# Connectors.net
KiCad netlist of a schematic drawn in Altium Designer
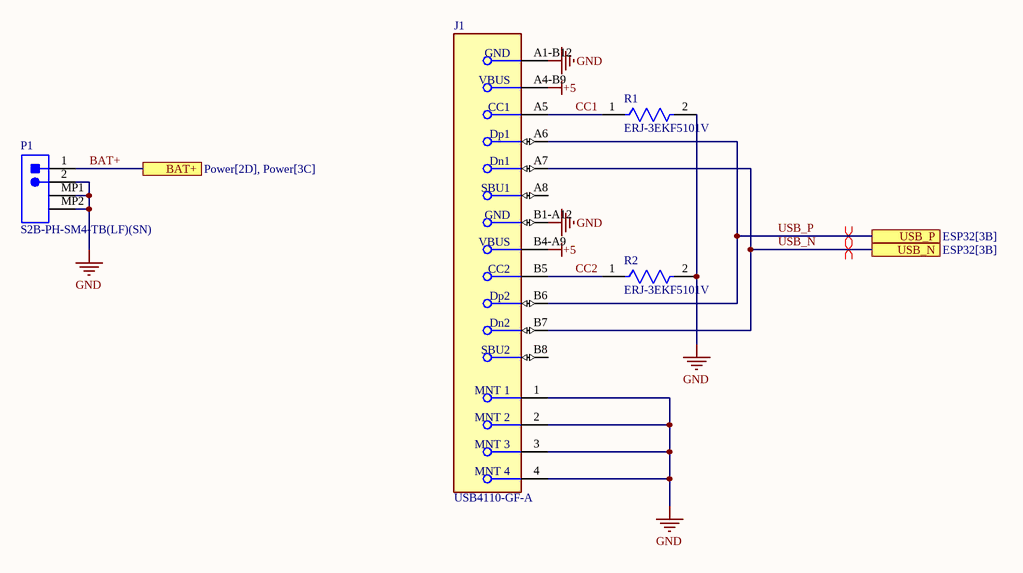
[diagram p0: Connectors.SchDoc]

(export (version "E")
  (design (tool "Eeschema 10.0.6"))
  (components
    (comp (ref "J1")
      (value "USB4110-GF-A")
      (footprint "FP-USB4110-GF-A-MFG")
      (description "CONN USB 2.0 TYPE-C R/A SMT")
      (fields
        (field (name "OCTOPART") "https://octopart.com/usb4110-gf-a-gct-103941985")
        (field (name "MANUFACTURER") "GCT")
      )
      (libsource (lib "Altium Content Vault") (part "e23f2b38bb3c3f98e683ebab9ede730"))
    )
    (comp (ref "P1")
      (value "S2B-PH-SM4-TB(LF)(SN)")
      (footprint "JST- S2B-PH-SM4-TB(LF)(SN)-2_V")
      (description "Male Header, Pitch 2 mm, 1 x 2 Position, Height 5.5 mm, -25 to 85 degC, RoHS, Tape and Reel")
      (libsource (lib "Altium Content Vault") (part "CN-1P-2M-R2"))
    )
    (comp (ref "R1")
      (value "ERJ-3EKF5101V")
      (footprint "FP-ERJ3EK-MFG")
      (description "RES SMD 5.1K OHM 1% 1/10W 0603")
      (fields (field (name "TOLERANCE") "1%"))
      (libsource (lib "Altium Content Vault") (part "1029c3af85768c4190bb7ad29bc67b5"))
    )
    (comp (ref "R2")
      (value "ERJ-3EKF5101V")
      (footprint "FP-ERJ3EK-MFG")
      (description "RES SMD 5.1K OHM 1% 1/10W 0603")
      (fields (field (name "TOLERANCE") "1%"))
      (libsource (lib "Altium Content Vault") (part "1029c3af85768c4190bb7ad29bc67b5"))
    )
  )
  (nets
    (net (code "1") (name "+5") (class "Default")
      (node (ref "J1") (pin "A4-B9") (pinfunction "VBUS_A4-B9") (pintype "power_in"))
      (node (ref "J1") (pin "B4-A9") (pinfunction "VBUS_B4-A9") (pintype "power_in"))
    )
    (net (code "2") (name "/BAT+") (class "Default")
      (node (ref "P1") (pin "1") (pinfunction "1_1") (pintype "passive"))
    )
    (net (code "3") (name "/CC1") (class "Default")
      (node (ref "J1") (pin "A5") (pinfunction "CC1_A5") (pintype "power_in"))
      (node (ref "R1") (pin "1") (pinfunction "1_1") (pintype "passive"))
    )
    (net (code "4") (name "/CC2") (class "Default")
      (node (ref "J1") (pin "B5") (pinfunction "CC2_B5") (pintype "power_in"))
      (node (ref "R2") (pin "1") (pinfunction "1_1") (pintype "passive"))
    )
    (net (code "5") (name "/USB_N") (class "Default")
      (node (ref "J1") (pin "A7") (pinfunction "Dn1_A7") (pintype "bidirectional"))
      (node (ref "J1") (pin "B7") (pinfunction "Dn2_B7") (pintype "bidirectional"))
    )
    (net (code "6") (name "/USB_P") (class "Default")
      (node (ref "J1") (pin "A6") (pinfunction "Dp1_A6") (pintype "bidirectional"))
      (node (ref "J1") (pin "B6") (pinfunction "Dp2_B6") (pintype "bidirectional"))
    )
    (net (code "7") (name "GND") (class "Default")
      (node (ref "J1") (pin "1") (pinfunction "MNT_1_1") (pintype "passive"))
      (node (ref "J1") (pin "2") (pinfunction "MNT_2_2") (pintype "passive"))
      (node (ref "J1") (pin "3") (pinfunction "MNT_3_3") (pintype "passive"))
      (node (ref "J1") (pin "4") (pinfunction "MNT_4_4") (pintype "passive"))
      (node (ref "J1") (pin "A1-B12") (pinfunction "GND_A1-B12") (pintype "passive"))
      (node (ref "J1") (pin "B1-A12") (pinfunction "GND_B1-A12") (pintype "bidirectional"))
      (node (ref "P1") (pin "2") (pinfunction "2_2") (pintype "passive"))
      (node (ref "P1") (pin "MP1") (pinfunction "MP1_MP1") (pintype "passive"))
      (node (ref "P1") (pin "MP2") (pinfunction "MP2_MP2") (pintype "passive"))
      (node (ref "R1") (pin "2") (pinfunction "2_2") (pintype "passive"))
      (node (ref "R2") (pin "2") (pinfunction "2_2") (pintype "passive"))
    )
    (net (code "8") (name "unconnected-(J1-SBU1-PadA8)") (class "Default")
      (node (ref "J1") (pin "A8") (pinfunction "SBU1_A8") (pintype "bidirectional"))
    )
    (net (code "9") (name "unconnected-(J1-SBU2-PadB8)") (class "Default")
      (node (ref "J1") (pin "B8") (pinfunction "SBU2_B8") (pintype "bidirectional"))
    )
  )
)
